# robber_v01.net
KiCad netlist of a schematic drawn in EAGLE
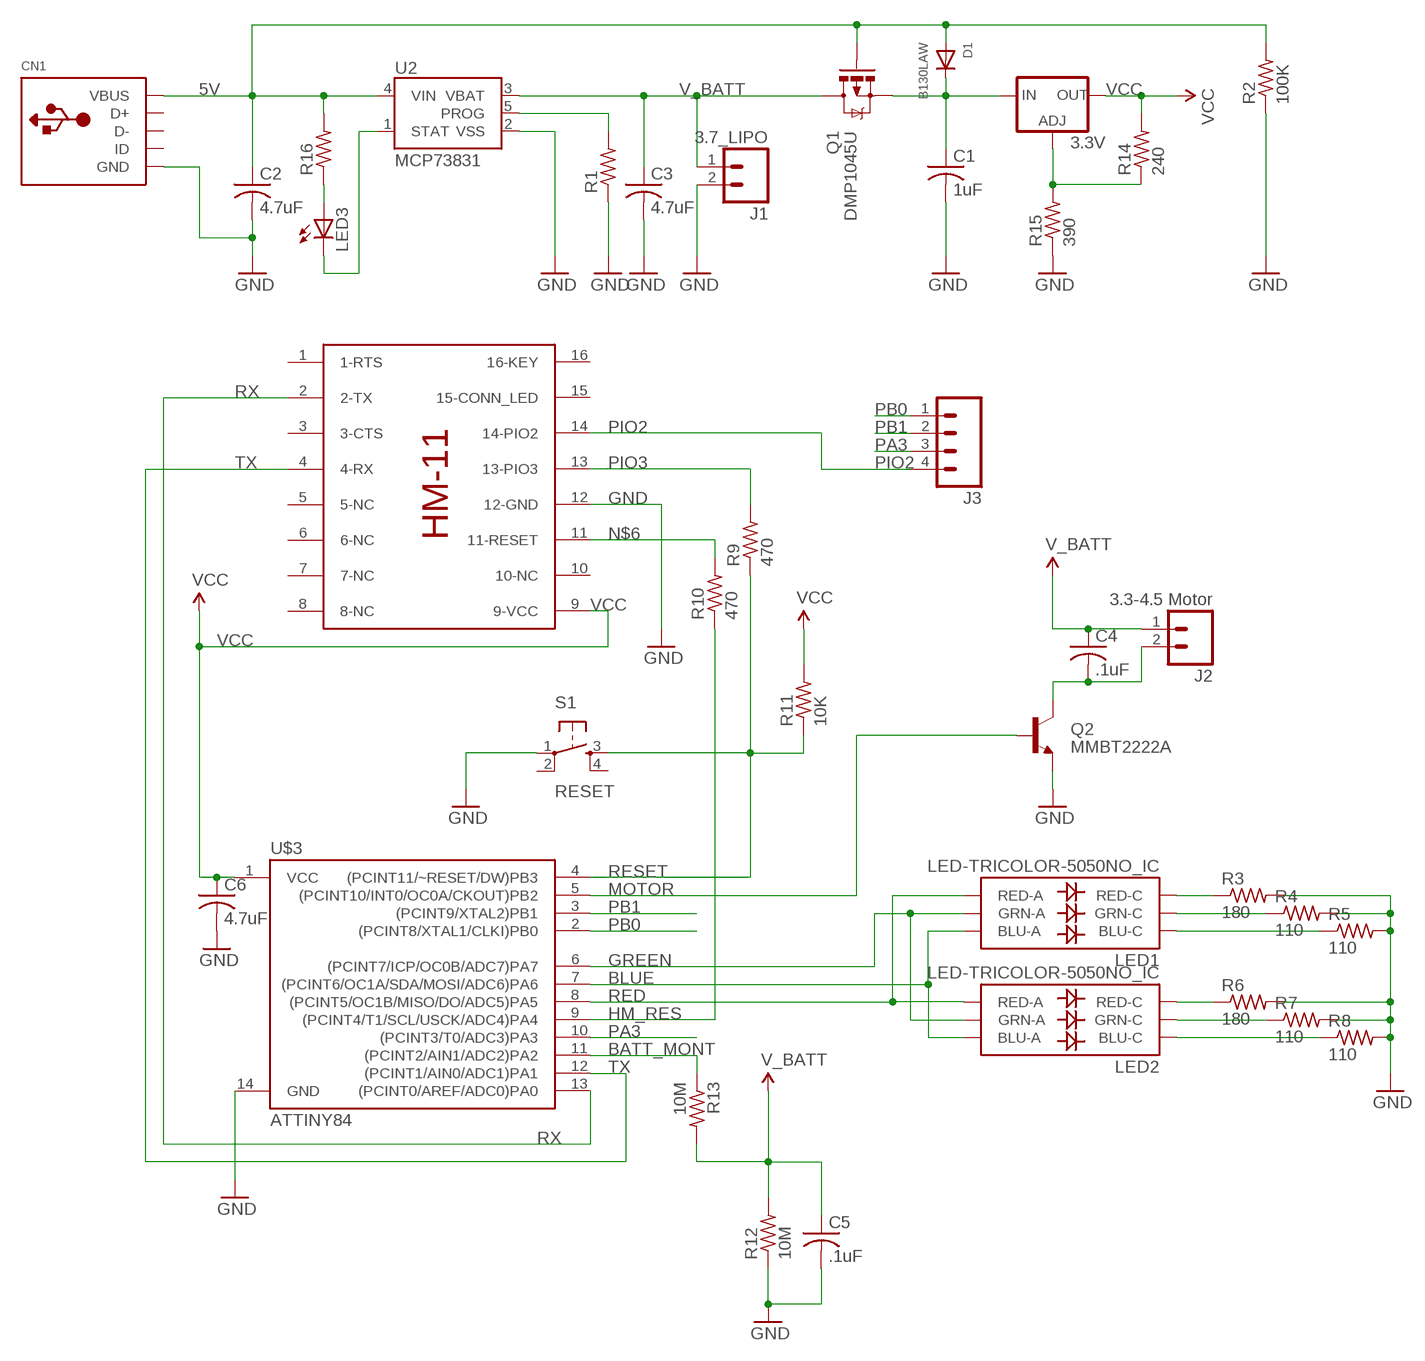
[diagram p0: schematic, sheet 1]

(export (version "E")
  (design (tool "Eeschema 10.0.6"))
  (components
    (comp (ref "3.3V")
      (value "V_REG_317SMD")
      (footprint "eagle-import:SOT223")
      (libsource (lib "eagle-import") (part "V_REG_317SMD"))
    )
    (comp (ref "C1")
      (value "1uF")
      (footprint "eagle-import:C0805")
      (libsource (lib "eagle-import") (part "C-USC0805"))
    )
    (comp (ref "C2")
      (value "4.7uF")
      (footprint "eagle-import:C0805")
      (libsource (lib "eagle-import") (part "C-USC0805"))
    )
    (comp (ref "C3")
      (value "4.7uF")
      (footprint "eagle-import:C0805")
      (libsource (lib "eagle-import") (part "C-USC0805"))
    )
    (comp (ref "C4")
      (value ".1uF")
      (footprint "eagle-import:C0805")
      (libsource (lib "eagle-import") (part "C-USC0805"))
    )
    (comp (ref "C5")
      (value ".1uF")
      (footprint "eagle-import:C0805")
      (libsource (lib "eagle-import") (part "C-USC0805"))
    )
    (comp (ref "C6")
      (value "4.7uF")
      (footprint "eagle-import:C0805")
      (libsource (lib "eagle-import") (part "C-USC0805"))
    )
    (comp (ref "CN1")
      (value "USBMINIB")
      (footprint "eagle-import:USB-MINIB")
      (libsource (lib "eagle-import") (part "USBMINIB"))
    )
    (comp (ref "D1")
      (value "B130LAW")
      (footprint "eagle-import:SOD-123")
      (libsource (lib "eagle-import") (part "DIODESOD-123"))
    )
    (comp (ref "J1")
      (value "3.7_LIPO")
      (footprint "eagle-import:1X02")
      (libsource (lib "eagle-import") (part "M02PTH"))
    )
    (comp (ref "J2")
      (value "3.3-4.5 Motor")
      (footprint "eagle-import:1X02")
      (libsource (lib "eagle-import") (part "M02PTH"))
    )
    (comp (ref "J3")
      (value "M04PTH")
      (footprint "eagle-import:1X04")
      (libsource (lib "eagle-import") (part "M04PTH"))
    )
    (comp (ref "LED1")
      (value "LED-TRICOLOR-5050NO_IC")
      (footprint "eagle-import:LED-TRICOLOR-5050")
      (libsource (lib "eagle-import") (part "LED-TRICOLOR-5050NO_IC"))
    )
    (comp (ref "LED2")
      (value "LED-TRICOLOR-5050NO_IC")
      (footprint "eagle-import:LED-TRICOLOR-5050")
      (libsource (lib "eagle-import") (part "LED-TRICOLOR-5050NO_IC"))
    )
    (comp (ref "LED3")
      (value "LEDSML0603")
      (footprint "eagle-import:SML0603")
      (libsource (lib "eagle-import") (part "LEDSML0603"))
    )
    (comp (ref "Q1")
      (value "DMP1045U")
      (footprint "eagle-import:SOT23-3")
      (libsource (lib "eagle-import") (part "MOSFET-PCHANNEL"))
    )
    (comp (ref "Q2")
      (value "MMBT2222A")
      (footprint "eagle-import:SOT23-3")
      (libsource (lib "eagle-import") (part "TRANSISTOR_NPNMMBT2222A"))
    )
    (comp (ref "R1")
      (value "R-US_R0805")
      (footprint "eagle-import:R0805")
      (libsource (lib "eagle-import") (part "R-US_R0805"))
    )
    (comp (ref "R2")
      (value "100K")
      (footprint "eagle-import:R0805")
      (libsource (lib "eagle-import") (part "R-US_R0805"))
    )
    (comp (ref "R3")
      (value "180")
      (footprint "eagle-import:R0805")
      (libsource (lib "eagle-import") (part "R-US_R0805"))
    )
    (comp (ref "R4")
      (value "110")
      (footprint "eagle-import:R0805")
      (libsource (lib "eagle-import") (part "R-US_R0805"))
    )
    (comp (ref "R5")
      (value "110")
      (footprint "eagle-import:R0805")
      (libsource (lib "eagle-import") (part "R-US_R0805"))
    )
    (comp (ref "R6")
      (value "180")
      (footprint "eagle-import:R0805")
      (libsource (lib "eagle-import") (part "R-US_R0805"))
    )
    (comp (ref "R7")
      (value "110")
      (footprint "eagle-import:R0805")
      (libsource (lib "eagle-import") (part "R-US_R0805"))
    )
    (comp (ref "R8")
      (value "110")
      (footprint "eagle-import:R0805")
      (libsource (lib "eagle-import") (part "R-US_R0805"))
    )
    (comp (ref "R9")
      (value "470")
      (footprint "eagle-import:R0805")
      (libsource (lib "eagle-import") (part "R-US_R0805"))
    )
    (comp (ref "R10")
      (value "470")
      (footprint "eagle-import:R0805")
      (libsource (lib "eagle-import") (part "R-US_R0805"))
    )
    (comp (ref "R11")
      (value "10K")
      (footprint "eagle-import:R0805")
      (libsource (lib "eagle-import") (part "R-US_R0805"))
    )
    (comp (ref "R12")
      (value "10M")
      (footprint "eagle-import:R0805")
      (libsource (lib "eagle-import") (part "R-US_R0805"))
    )
    (comp (ref "R13")
      (value "10M")
      (footprint "eagle-import:R0805")
      (libsource (lib "eagle-import") (part "R-US_R0805"))
    )
    (comp (ref "R14")
      (value "240")
      (footprint "eagle-import:R0805")
      (libsource (lib "eagle-import") (part "R-US_R0805"))
    )
    (comp (ref "R15")
      (value "390")
      (footprint "eagle-import:R0805")
      (libsource (lib "eagle-import") (part "R-US_R0805"))
    )
    (comp (ref "R16")
      (value "R-US_R0805")
      (footprint "eagle-import:R0805")
      (libsource (lib "eagle-import") (part "R-US_R0805"))
    )
    (comp (ref "S1")
      (value "RESET")
      (footprint "eagle-import:TACTILE-SWITCH-SMD")
      (libsource (lib "eagle-import") (part "TAC_SWITCHSMD"))
    )
    (comp (ref "U$1")
      (value "HM-11")
      (footprint "eagle-import:HM-11")
      (libsource (lib "eagle-import") (part "HM-11"))
    )
    (comp (ref "U$3")
      (value "ATTINY84")
      (footprint "eagle-import:SO14")
      (libsource (lib "eagle-import") (part "ATTINY84"))
    )
    (comp (ref "U2")
      (value "MCP73831")
      (footprint "eagle-import:SOT23-5")
      (libsource (lib "eagle-import") (part "MCP73831"))
    )
  )
  (nets
    (net (code "1") (name "/5V") (class "Default")
      (node (ref "C2") (pin "1") (pinfunction "1_1") (pintype "passive"))
      (node (ref "CN1") (pin "VBUS") (pinfunction "VBUS_VBUS") (pintype "power_in"))
      (node (ref "D1") (pin "A") (pinfunction "A_A") (pintype "passive"))
      (node (ref "Q1") (pin "1") (pinfunction "G_1") (pintype "passive"))
      (node (ref "R16") (pin "2") (pinfunction "2_2") (pintype "passive"))
      (node (ref "R2") (pin "2") (pinfunction "2_2") (pintype "passive"))
      (node (ref "U2") (pin "4") (pinfunction "VIN_4") (pintype "power_in"))
    )
    (net (code "2") (name "/BATT_MONT") (class "Default")
      (node (ref "R13") (pin "1") (pinfunction "1_1") (pintype "passive"))
      (node (ref "U$3") (pin "11") (pinfunction "(PCINT2/AIN1/ADC2)PA2_11") (pintype "bidirectional"))
    )
    (net (code "3") (name "/BLUE") (class "Default")
      (node (ref "LED1") (pin "3") (pinfunction "BLU-A_3") (pintype "bidirectional"))
      (node (ref "LED2") (pin "3") (pinfunction "BLU-A_3") (pintype "bidirectional"))
      (node (ref "U$3") (pin "7") (pinfunction "(PCINT6/OC1A/SDA/MOSI/ADC6)PA6_7") (pintype "bidirectional"))
    )
    (net (code "4") (name "/GREEN") (class "Default")
      (node (ref "LED1") (pin "1") (pinfunction "GRN-A_1") (pintype "bidirectional"))
      (node (ref "LED2") (pin "1") (pinfunction "GRN-A_1") (pintype "bidirectional"))
      (node (ref "U$3") (pin "6") (pinfunction "(PCINT7/ICP/OC0B/ADC7)PA7_6") (pintype "bidirectional"))
    )
    (net (code "5") (name "/HM_RES") (class "Default")
      (node (ref "R10") (pin "1") (pinfunction "1_1") (pintype "passive"))
      (node (ref "U$3") (pin "9") (pinfunction "(PCINT4/T1/SCL/USCK/ADC4)PA4_9") (pintype "bidirectional"))
    )
    (net (code "6") (name "/MOTOR") (class "Default")
      (node (ref "Q2") (pin "1") (pinfunction "B_1") (pintype "passive"))
      (node (ref "U$3") (pin "5") (pinfunction "(PCINT10/INT0/OC0A/CKOUT)PB2_5") (pintype "bidirectional"))
    )
    (net (code "7") (name "/N$6") (class "Default")
      (node (ref "R10") (pin "2") (pinfunction "2_2") (pintype "passive"))
      (node (ref "U$1") (pin "11") (pinfunction "11-RESET_11") (pintype "bidirectional"))
    )
    (net (code "8") (name "/PA3") (class "Default")
      (node (ref "J3") (pin "3") (pinfunction "3_3") (pintype "passive"))
      (node (ref "U$3") (pin "10") (pinfunction "(PCINT3/T0/ADC3)PA3_10") (pintype "bidirectional"))
    )
    (net (code "9") (name "/PB0") (class "Default")
      (node (ref "J3") (pin "1") (pinfunction "1_1") (pintype "passive"))
      (node (ref "U$3") (pin "2") (pinfunction "(PCINT8/XTAL1/CLKI)PB0_2") (pintype "bidirectional"))
    )
    (net (code "10") (name "/PB1") (class "Default")
      (node (ref "J3") (pin "2") (pinfunction "2_2") (pintype "passive"))
      (node (ref "U$3") (pin "3") (pinfunction "(PCINT9/XTAL2)PB1_3") (pintype "bidirectional"))
    )
    (net (code "11") (name "/PIO2") (class "Default")
      (node (ref "J3") (pin "4") (pinfunction "4_4") (pintype "passive"))
      (node (ref "U$1") (pin "14") (pinfunction "14-PIO2_14") (pintype "bidirectional"))
    )
    (net (code "12") (name "/PIO3") (class "Default")
      (node (ref "R9") (pin "2") (pinfunction "2_2") (pintype "passive"))
      (node (ref "U$1") (pin "13") (pinfunction "13-PIO3_13") (pintype "bidirectional"))
    )
    (net (code "13") (name "/RED") (class "Default")
      (node (ref "LED1") (pin "2") (pinfunction "RED-A_2") (pintype "bidirectional"))
      (node (ref "LED2") (pin "2") (pinfunction "RED-A_2") (pintype "bidirectional"))
      (node (ref "U$3") (pin "8") (pinfunction "(PCINT5/OC1B/MISO/DO/ADC5)PA5_8") (pintype "bidirectional"))
    )
    (net (code "14") (name "/RESET") (class "Default")
      (node (ref "R11") (pin "1") (pinfunction "1_1") (pintype "passive"))
      (node (ref "R9") (pin "1") (pinfunction "1_1") (pintype "passive"))
      (node (ref "S1") (pin "3") (pinfunction "3_3") (pintype "passive"))
      (node (ref "U$3") (pin "4") (pinfunction "(PCINT11/~{RESET/DW})PB3_4") (pintype "bidirectional"))
    )
    (net (code "15") (name "/RX") (class "Default")
      (node (ref "U$1") (pin "2") (pinfunction "2-TX_2") (pintype "bidirectional"))
      (node (ref "U$3") (pin "13") (pinfunction "(PCINT0/AREF/ADC0)PA0_13") (pintype "bidirectional"))
    )
    (net (code "16") (name "/TX") (class "Default")
      (node (ref "U$1") (pin "4") (pinfunction "4-RX_4") (pintype "bidirectional"))
      (node (ref "U$3") (pin "12") (pinfunction "(PCINT1/AIN0/ADC1)PA1_12") (pintype "bidirectional"))
    )
    (net (code "17") (name "GND") (class "Default")
      (node (ref "C1") (pin "2") (pinfunction "2_2") (pintype "passive"))
      (node (ref "C2") (pin "2") (pinfunction "2_2") (pintype "passive"))
      (node (ref "C3") (pin "2") (pinfunction "2_2") (pintype "passive"))
      (node (ref "C5") (pin "2") (pinfunction "2_2") (pintype "passive"))
      (node (ref "C6") (pin "2") (pinfunction "2_2") (pintype "passive"))
      (node (ref "CN1") (pin "GND") (pinfunction "GND_GND") (pintype "power_in"))
      (node (ref "CN1") (pin "GND1") (pinfunction "GND_GND1") (pintype "power_in"))
      (node (ref "CN1") (pin "GND2") (pinfunction "GND_GND2") (pintype "power_in"))
      (node (ref "CN1") (pin "GND3") (pinfunction "GND_GND3") (pintype "power_in"))
      (node (ref "CN1") (pin "GND4") (pinfunction "GND_GND4") (pintype "power_in"))
      (node (ref "J1") (pin "2") (pinfunction "2_2") (pintype "passive"))
      (node (ref "Q2") (pin "2") (pinfunction "E_2") (pintype "passive"))
      (node (ref "R1") (pin "1") (pinfunction "1_1") (pintype "passive"))
      (node (ref "R12") (pin "1") (pinfunction "1_1") (pintype "passive"))
      (node (ref "R15") (pin "1") (pinfunction "1_1") (pintype "passive"))
      (node (ref "R2") (pin "1") (pinfunction "1_1") (pintype "passive"))
      (node (ref "R3") (pin "2") (pinfunction "2_2") (pintype "passive"))
      (node (ref "R4") (pin "2") (pinfunction "2_2") (pintype "passive"))
      (node (ref "R5") (pin "2") (pinfunction "2_2") (pintype "passive"))
      (node (ref "R6") (pin "2") (pinfunction "2_2") (pintype "passive"))
      (node (ref "R7") (pin "2") (pinfunction "2_2") (pintype "passive"))
      (node (ref "R8") (pin "2") (pinfunction "2_2") (pintype "passive"))
      (node (ref "S1") (pin "1") (pinfunction "1_1") (pintype "passive"))
      (node (ref "U$1") (pin "12") (pinfunction "12-GND_12") (pintype "bidirectional"))
      (node (ref "U$3") (pin "14") (pinfunction "GND_14") (pintype "bidirectional"))
      (node (ref "U2") (pin "2") (pinfunction "VSS_2") (pintype "power_in"))
    )
    (net (code "18") (name "Net-(3.3V-ADJ)") (class "Default")
      (node (ref "3.3V") (pin "1") (pinfunction "ADJ_1") (pintype "input"))
      (node (ref "R14") (pin "1") (pinfunction "1_1") (pintype "passive"))
      (node (ref "R15") (pin "2") (pinfunction "2_2") (pintype "passive"))
    )
    (net (code "19") (name "Net-(3.3V-IN)") (class "Default")
      (node (ref "3.3V") (pin "3") (pinfunction "IN_3") (pintype "input"))
      (node (ref "C1") (pin "1") (pinfunction "1_1") (pintype "passive"))
      (node (ref "D1") (pin "C") (pinfunction "C_C") (pintype "passive"))
      (node (ref "Q1") (pin "2") (pinfunction "S_2") (pintype "passive"))
    )
    (net (code "20") (name "Net-(LED1-BLU-C)") (class "Default")
      (node (ref "LED1") (pin "4") (pinfunction "BLU-C_4") (pintype "bidirectional"))
      (node (ref "R5") (pin "1") (pinfunction "1_1") (pintype "passive"))
    )
    (net (code "21") (name "Net-(LED1-GRN-C)") (class "Default")
      (node (ref "LED1") (pin "6") (pinfunction "GRN-C_6") (pintype "bidirectional"))
      (node (ref "R4") (pin "1") (pinfunction "1_1") (pintype "passive"))
    )
    (net (code "22") (name "Net-(LED1-RED-C)") (class "Default")
      (node (ref "LED1") (pin "5") (pinfunction "RED-C_5") (pintype "bidirectional"))
      (node (ref "R3") (pin "1") (pinfunction "1_1") (pintype "passive"))
    )
    (net (code "23") (name "Net-(LED2-BLU-C)") (class "Default")
      (node (ref "LED2") (pin "4") (pinfunction "BLU-C_4") (pintype "bidirectional"))
      (node (ref "R8") (pin "1") (pinfunction "1_1") (pintype "passive"))
    )
    (net (code "24") (name "Net-(LED2-GRN-C)") (class "Default")
      (node (ref "LED2") (pin "6") (pinfunction "GRN-C_6") (pintype "bidirectional"))
      (node (ref "R7") (pin "1") (pinfunction "1_1") (pintype "passive"))
    )
    (net (code "25") (name "Net-(LED2-RED-C)") (class "Default")
      (node (ref "LED2") (pin "5") (pinfunction "RED-C_5") (pintype "bidirectional"))
      (node (ref "R6") (pin "1") (pinfunction "1_1") (pintype "passive"))
    )
    (net (code "26") (name "Net-(LED3-PadA)") (class "Default")
      (node (ref "LED3") (pin "A") (pinfunction "A_A") (pintype "passive"))
      (node (ref "R16") (pin "1") (pinfunction "1_1") (pintype "passive"))
    )
    (net (code "27") (name "Net-(Q2-C)") (class "Default")
      (node (ref "C4") (pin "2") (pinfunction "2_2") (pintype "passive"))
      (node (ref "J2") (pin "2") (pinfunction "2_2") (pintype "passive"))
      (node (ref "Q2") (pin "3") (pinfunction "C_3") (pintype "passive"))
    )
    (net (code "28") (name "Net-(U2-PROG)") (class "Default")
      (node (ref "R1") (pin "2") (pinfunction "2_2") (pintype "passive"))
      (node (ref "U2") (pin "5") (pinfunction "PROG_5") (pintype "input"))
    )
    (net (code "29") (name "Net-(U2-STAT)") (class "Default")
      (node (ref "LED3") (pin "C") (pinfunction "C_C") (pintype "passive"))
      (node (ref "U2") (pin "1") (pinfunction "STAT_1") (pintype "output"))
    )
    (net (code "30") (name "VCC") (class "Default")
      (node (ref "3.3V") (pin "2") (pinfunction "OUT_2") (pintype "output"))
      (node (ref "C6") (pin "1") (pinfunction "1_1") (pintype "passive"))
      (node (ref "R11") (pin "2") (pinfunction "2_2") (pintype "passive"))
      (node (ref "R14") (pin "2") (pinfunction "2_2") (pintype "passive"))
      (node (ref "U$1") (pin "9") (pinfunction "9-VCC_9") (pintype "bidirectional"))
      (node (ref "U$3") (pin "1") (pinfunction "VCC_1") (pintype "bidirectional"))
    )
    (net (code "31") (name "V_BATT") (class "Default")
      (node (ref "C3") (pin "1") (pinfunction "1_1") (pintype "passive"))
      (node (ref "C4") (pin "1") (pinfunction "1_1") (pintype "passive"))
      (node (ref "C5") (pin "1") (pinfunction "1_1") (pintype "passive"))
      (node (ref "J1") (pin "1") (pinfunction "1_1") (pintype "passive"))
      (node (ref "J2") (pin "1") (pinfunction "1_1") (pintype "passive"))
      (node (ref "Q1") (pin "3") (pinfunction "D_3") (pintype "passive"))
      (node (ref "R12") (pin "2") (pinfunction "2_2") (pintype "passive"))
      (node (ref "R13") (pin "2") (pinfunction "2_2") (pintype "passive"))
      (node (ref "U2") (pin "3") (pinfunction "VBAT_3") (pintype "power_in"))
    )
    (net (code "32") (name "unconnected-(CN1-PadD+)") (class "Default")
      (node (ref "CN1") (pin "D+") (pinfunction "D+_D+") (pintype "bidirectional"))
    )
    (net (code "33") (name "unconnected-(CN1-PadD-)") (class "Default")
      (node (ref "CN1") (pin "D-") (pinfunction "D-_D-") (pintype "bidirectional"))
    )
    (net (code "34") (name "unconnected-(CN1-PadID)") (class "Default")
      (node (ref "CN1") (pin "ID") (pinfunction "ID_ID") (pintype "bidirectional"))
    )
    (net (code "35") (name "unconnected-(S1-Pad2)") (class "Default")
      (node (ref "S1") (pin "2") (pinfunction "2_2") (pintype "passive"))
    )
    (net (code "36") (name "unconnected-(S1-Pad4)") (class "Default")
      (node (ref "S1") (pin "4") (pinfunction "4_4") (pintype "passive"))
    )
    (net (code "37") (name "unconnected-(U$1-1-RTS-Pad1)") (class "Default")
      (node (ref "U$1") (pin "1") (pinfunction "1-RTS_1") (pintype "bidirectional"))
    )
    (net (code "38") (name "unconnected-(U$1-3-CTS-Pad3)") (class "Default")
      (node (ref "U$1") (pin "3") (pinfunction "3-CTS_3") (pintype "bidirectional"))
    )
    (net (code "39") (name "unconnected-(U$1-5-NC-Pad5)") (class "Default")
      (node (ref "U$1") (pin "5") (pinfunction "5-NC_5") (pintype "bidirectional"))
    )
    (net (code "40") (name "unconnected-(U$1-6-NC-Pad6)") (class "Default")
      (node (ref "U$1") (pin "6") (pinfunction "6-NC_6") (pintype "bidirectional"))
    )
    (net (code "41") (name "unconnected-(U$1-7-NC-Pad7)") (class "Default")
      (node (ref "U$1") (pin "7") (pinfunction "7-NC_7") (pintype "bidirectional"))
    )
    (net (code "42") (name "unconnected-(U$1-8-NC-Pad8)") (class "Default")
      (node (ref "U$1") (pin "8") (pinfunction "8-NC_8") (pintype "bidirectional"))
    )
    (net (code "43") (name "unconnected-(U$1-10-NC-Pad10)") (class "Default")
      (node (ref "U$1") (pin "10") (pinfunction "10-NC_10") (pintype "bidirectional"))
    )
    (net (code "44") (name "unconnected-(U$1-15-CONN_LED-Pad15)") (class "Default")
      (node (ref "U$1") (pin "15") (pinfunction "15-CONN_LED_15") (pintype "bidirectional"))
    )
    (net (code "45") (name "unconnected-(U$1-16-KEY-Pad16)") (class "Default")
      (node (ref "U$1") (pin "16") (pinfunction "16-KEY_16") (pintype "bidirectional"))
    )
  )
)
